# ProProject_Automatic_Night_Light_2025-07.net
KiCad netlist of a schematic drawn in EasyEDA Pro
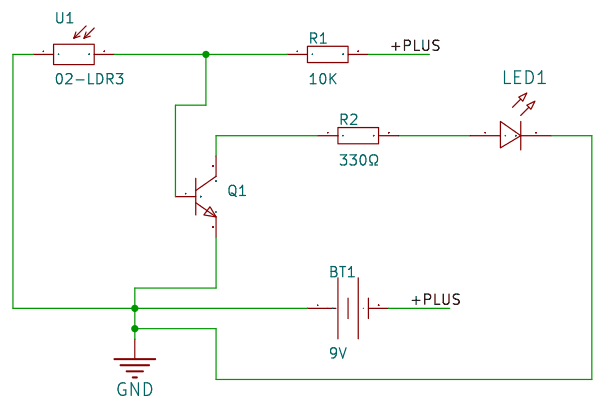
[diagram p0: schematic sheet]

(export (version "E")
  (design (tool "Eeschema 10.0.6"))
  (components
    (comp (ref "BT1")
      (value "9V")
      (footprint "easyedapro:BAT-TH_2P-9VBATTERY")
      (fields (field (name "Manufacturer") "Q&J"))
      (libsource (lib "easyedapro") (part "9V电池铜线扣 铜100MM"))
    )
    (comp (ref "LED1")
      (value "~")
      (footprint "easyedapro:LED0402-RD_YELLOW")
      (libsource (lib "easyedapro") (part "LED_R"))
    )
    (comp (ref "Q1")
      (value "~")
      (footprint "easyedapro:SOT-23_L2.9-W1.3-P1.90-LS2.4-BR")
      (libsource (lib "easyedapro") (part "NPN"))
    )
    (comp (ref "R1") (value "10K") (footprint "easyedapro:R0603") (libsource (lib "easyedapro") (part "Res")))
    (comp (ref "R2")
      (value "330Ω")
      (footprint "easyedapro:R0603")
      (libsource (lib "easyedapro") (part "Res"))
    )
    (comp (ref "U1")
      (value "02-LDR3")
      (footprint "easyedapro:RES-TH_L5.0-W4.3-P3.40-D0.5")
      (fields (field (name "Manufacturer") "NTE Electronics"))
      (libsource (lib "easyedapro") (part "02-LDR3"))
    )
  )
  (nets
    (net (code "1") (name "/+PLUS") (class "Default")
      (node (ref "BT1") (pin "2") (pinfunction "-_2") (pintype "unspecified"))
      (node (ref "R1") (pin "2") (pinfunction "2_2") (pintype "input"))
    )
    (net (code "2") (name "GND") (class "Default")
      (node (ref "BT1") (pin "1") (pinfunction "+_1") (pintype "unspecified"))
      (node (ref "LED1") (pin "2") (pinfunction "C_2") (pintype "input"))
      (node (ref "Q1") (pin "2") (pinfunction "E_2") (pintype "unspecified"))
      (node (ref "U1") (pin "1") (pinfunction "1_1") (pintype "unspecified"))
    )
    (net (code "3") (name "Net-(LED1-A)") (class "Default")
      (node (ref "LED1") (pin "1") (pinfunction "A_1") (pintype "input"))
      (node (ref "R2") (pin "2") (pinfunction "2_2") (pintype "input"))
    )
    (net (code "4") (name "Net-(Q1-B)") (class "Default")
      (node (ref "Q1") (pin "1") (pinfunction "B_1") (pintype "unspecified"))
      (node (ref "R1") (pin "1") (pinfunction "1_1") (pintype "input"))
      (node (ref "U1") (pin "2") (pinfunction "2_2") (pintype "unspecified"))
    )
    (net (code "5") (name "Net-(Q1-C)") (class "Default")
      (node (ref "Q1") (pin "3") (pinfunction "C_3") (pintype "unspecified"))
      (node (ref "R2") (pin "1") (pinfunction "1_1") (pintype "input"))
    )
  )
)
